# klavesnice.net
KiCad netlist of a schematic drawn in EAGLE
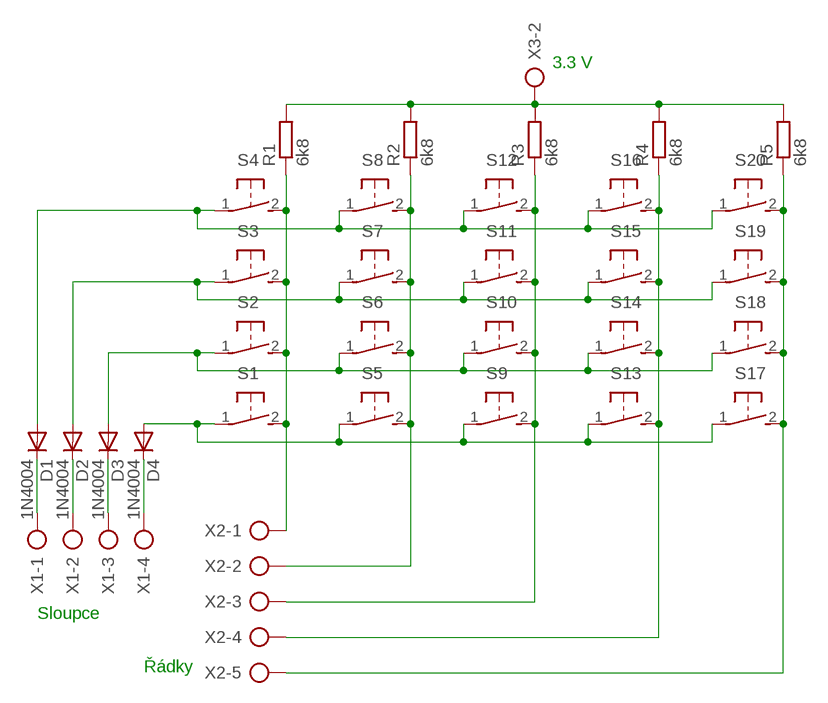
[diagram p0: schematic, sheet 1]

(export (version "E")
  (design (tool "Eeschema 10.0.6"))
  (components
    (comp (ref "D1")
      (value "1N4004")
      (footprint "eagle-import:DO41-10")
      (libsource (lib "eagle-import") (part "1N4004"))
    )
    (comp (ref "D2")
      (value "1N4004")
      (footprint "eagle-import:DO41-10")
      (libsource (lib "eagle-import") (part "1N4004"))
    )
    (comp (ref "D3")
      (value "1N4004")
      (footprint "eagle-import:DO41-10")
      (libsource (lib "eagle-import") (part "1N4004"))
    )
    (comp (ref "D4")
      (value "1N4004")
      (footprint "eagle-import:DO41-10")
      (libsource (lib "eagle-import") (part "1N4004"))
    )
    (comp (ref "R1")
      (value "6k8")
      (footprint "eagle-import:0207_12")
      (libsource (lib "eagle-import") (part "R-EU_0207/12"))
    )
    (comp (ref "R2")
      (value "6k8")
      (footprint "eagle-import:0207_12")
      (libsource (lib "eagle-import") (part "R-EU_0207/12"))
    )
    (comp (ref "R3")
      (value "6k8")
      (footprint "eagle-import:0207_12")
      (libsource (lib "eagle-import") (part "R-EU_0207/12"))
    )
    (comp (ref "R4")
      (value "6k8")
      (footprint "eagle-import:0207_12")
      (libsource (lib "eagle-import") (part "R-EU_0207/12"))
    )
    (comp (ref "R5")
      (value "6k8")
      (footprint "eagle-import:0207_12")
      (libsource (lib "eagle-import") (part "R-EU_0207/12"))
    )
    (comp (ref "S1")
      (value "31-XX")
      (footprint "eagle-import:B3F-31XX")
      (fields (field (name "MPN") "B3F-3100"))
      (libsource (lib "eagle-import") (part "31-XX"))
    )
    (comp (ref "S2")
      (value "31-XX")
      (footprint "eagle-import:B3F-31XX")
      (fields (field (name "MPN") "B3F-3100"))
      (libsource (lib "eagle-import") (part "31-XX"))
    )
    (comp (ref "S3")
      (value "31-XX")
      (footprint "eagle-import:B3F-31XX")
      (fields (field (name "MPN") "B3F-3100"))
      (libsource (lib "eagle-import") (part "31-XX"))
    )
    (comp (ref "S4")
      (value "31-XX")
      (footprint "eagle-import:B3F-31XX")
      (fields (field (name "MPN") "B3F-3100"))
      (libsource (lib "eagle-import") (part "31-XX"))
    )
    (comp (ref "S5")
      (value "31-XX")
      (footprint "eagle-import:B3F-31XX")
      (fields (field (name "MPN") "B3F-3100"))
      (libsource (lib "eagle-import") (part "31-XX"))
    )
    (comp (ref "S6")
      (value "31-XX")
      (footprint "eagle-import:B3F-31XX")
      (fields (field (name "MPN") "B3F-3100"))
      (libsource (lib "eagle-import") (part "31-XX"))
    )
    (comp (ref "S7")
      (value "31-XX")
      (footprint "eagle-import:B3F-31XX")
      (fields (field (name "MPN") "B3F-3100"))
      (libsource (lib "eagle-import") (part "31-XX"))
    )
    (comp (ref "S8")
      (value "31-XX")
      (footprint "eagle-import:B3F-31XX")
      (fields (field (name "MPN") "B3F-3100"))
      (libsource (lib "eagle-import") (part "31-XX"))
    )
    (comp (ref "S9")
      (value "31-XX")
      (footprint "eagle-import:B3F-31XX")
      (fields (field (name "MPN") "B3F-3100"))
      (libsource (lib "eagle-import") (part "31-XX"))
    )
    (comp (ref "S10")
      (value "31-XX")
      (footprint "eagle-import:B3F-31XX")
      (fields (field (name "MPN") "B3F-3100"))
      (libsource (lib "eagle-import") (part "31-XX"))
    )
    (comp (ref "S11")
      (value "31-XX")
      (footprint "eagle-import:B3F-31XX")
      (fields (field (name "MPN") "B3F-3100"))
      (libsource (lib "eagle-import") (part "31-XX"))
    )
    (comp (ref "S12")
      (value "31-XX")
      (footprint "eagle-import:B3F-31XX")
      (fields (field (name "MPN") "B3F-3100"))
      (libsource (lib "eagle-import") (part "31-XX"))
    )
    (comp (ref "S13")
      (value "31-XX")
      (footprint "eagle-import:B3F-31XX")
      (fields (field (name "MPN") "B3F-3100"))
      (libsource (lib "eagle-import") (part "31-XX"))
    )
    (comp (ref "S14")
      (value "31-XX")
      (footprint "eagle-import:B3F-31XX")
      (fields (field (name "MPN") "B3F-3100"))
      (libsource (lib "eagle-import") (part "31-XX"))
    )
    (comp (ref "S15")
      (value "31-XX")
      (footprint "eagle-import:B3F-31XX")
      (fields (field (name "MPN") "B3F-3100"))
      (libsource (lib "eagle-import") (part "31-XX"))
    )
    (comp (ref "S16")
      (value "31-XX")
      (footprint "eagle-import:B3F-31XX")
      (fields (field (name "MPN") "B3F-3100"))
      (libsource (lib "eagle-import") (part "31-XX"))
    )
    (comp (ref "S17")
      (value "31-XX")
      (footprint "eagle-import:B3F-31XX")
      (fields (field (name "MPN") "B3F-3100"))
      (libsource (lib "eagle-import") (part "31-XX"))
    )
    (comp (ref "S18")
      (value "31-XX")
      (footprint "eagle-import:B3F-31XX")
      (fields (field (name "MPN") "B3F-3100"))
      (libsource (lib "eagle-import") (part "31-XX"))
    )
    (comp (ref "S19")
      (value "31-XX")
      (footprint "eagle-import:B3F-31XX")
      (fields (field (name "MPN") "B3F-3100"))
      (libsource (lib "eagle-import") (part "31-XX"))
    )
    (comp (ref "S20")
      (value "31-XX")
      (footprint "eagle-import:B3F-31XX")
      (fields (field (name "MPN") "B3F-3100"))
      (libsource (lib "eagle-import") (part "31-XX"))
    )
    (comp (ref "X1")
      (value "AK500/4-H")
      (footprint "eagle-import:AK500_4-H")
      (libsource (lib "eagle-import") (part "AK500/4-H"))
    )
    (comp (ref "X2")
      (value "AK500/5-H")
      (footprint "eagle-import:AK500_5-H")
      (libsource (lib "eagle-import") (part "AK500/5-H"))
    )
    (comp (ref "X3")
      (value "AK500/2-H")
      (footprint "eagle-import:AK500_2-H")
      (libsource (lib "eagle-import") (part "AK500/2-H"))
    )
  )
  (nets
    (net (code "1") (name "Net-(S1-P)") (class "Default")
      (node (ref "D4") (pin "A") (pinfunction "A_A") (pintype "passive"))
      (node (ref "S1") (pin "1") (pinfunction "P_1") (pintype "passive"))
      (node (ref "S13") (pin "1") (pinfunction "P_1") (pintype "passive"))
      (node (ref "S17") (pin "1") (pinfunction "P_1") (pintype "passive"))
      (node (ref "S5") (pin "1") (pinfunction "P_1") (pintype "passive"))
      (node (ref "S9") (pin "1") (pinfunction "P_1") (pintype "passive"))
    )
    (net (code "2") (name "Net-(S1-S)") (class "Default")
      (node (ref "R1") (pin "1") (pinfunction "1_1") (pintype "passive"))
      (node (ref "S1") (pin "2") (pinfunction "S_2") (pintype "passive"))
      (node (ref "S2") (pin "2") (pinfunction "S_2") (pintype "passive"))
      (node (ref "S3") (pin "2") (pinfunction "S_2") (pintype "passive"))
      (node (ref "S4") (pin "2") (pinfunction "S_2") (pintype "passive"))
      (node (ref "X2") (pin "1") (pinfunction "KL_1") (pintype "passive"))
    )
    (net (code "3") (name "Net-(S5-S)") (class "Default")
      (node (ref "R2") (pin "1") (pinfunction "1_1") (pintype "passive"))
      (node (ref "S5") (pin "2") (pinfunction "S_2") (pintype "passive"))
      (node (ref "S6") (pin "2") (pinfunction "S_2") (pintype "passive"))
      (node (ref "S7") (pin "2") (pinfunction "S_2") (pintype "passive"))
      (node (ref "S8") (pin "2") (pinfunction "S_2") (pintype "passive"))
      (node (ref "X2") (pin "2") (pinfunction "KL_2") (pintype "passive"))
    )
    (net (code "4") (name "Net-(S10-P)") (class "Default")
      (node (ref "D3") (pin "A") (pinfunction "A_A") (pintype "passive"))
      (node (ref "S10") (pin "1") (pinfunction "P_1") (pintype "passive"))
      (node (ref "S14") (pin "1") (pinfunction "P_1") (pintype "passive"))
      (node (ref "S18") (pin "1") (pinfunction "P_1") (pintype "passive"))
      (node (ref "S2") (pin "1") (pinfunction "P_1") (pintype "passive"))
      (node (ref "S6") (pin "1") (pinfunction "P_1") (pintype "passive"))
    )
    (net (code "5") (name "Net-(S10-S)") (class "Default")
      (node (ref "R3") (pin "1") (pinfunction "1_1") (pintype "passive"))
      (node (ref "S10") (pin "2") (pinfunction "S_2") (pintype "passive"))
      (node (ref "S11") (pin "2") (pinfunction "S_2") (pintype "passive"))
      (node (ref "S12") (pin "2") (pinfunction "S_2") (pintype "passive"))
      (node (ref "S9") (pin "2") (pinfunction "S_2") (pintype "passive"))
      (node (ref "X2") (pin "3") (pinfunction "KL_3") (pintype "passive"))
    )
    (net (code "6") (name "Net-(S11-P)") (class "Default")
      (node (ref "D2") (pin "A") (pinfunction "A_A") (pintype "passive"))
      (node (ref "S11") (pin "1") (pinfunction "P_1") (pintype "passive"))
      (node (ref "S15") (pin "1") (pinfunction "P_1") (pintype "passive"))
      (node (ref "S19") (pin "1") (pinfunction "P_1") (pintype "passive"))
      (node (ref "S3") (pin "1") (pinfunction "P_1") (pintype "passive"))
      (node (ref "S7") (pin "1") (pinfunction "P_1") (pintype "passive"))
    )
    (net (code "7") (name "Net-(S12-P)") (class "Default")
      (node (ref "D1") (pin "A") (pinfunction "A_A") (pintype "passive"))
      (node (ref "S12") (pin "1") (pinfunction "P_1") (pintype "passive"))
      (node (ref "S16") (pin "1") (pinfunction "P_1") (pintype "passive"))
      (node (ref "S20") (pin "1") (pinfunction "P_1") (pintype "passive"))
      (node (ref "S4") (pin "1") (pinfunction "P_1") (pintype "passive"))
      (node (ref "S8") (pin "1") (pinfunction "P_1") (pintype "passive"))
    )
    (net (code "8") (name "Net-(S13-S)") (class "Default")
      (node (ref "R4") (pin "1") (pinfunction "1_1") (pintype "passive"))
      (node (ref "S13") (pin "2") (pinfunction "S_2") (pintype "passive"))
      (node (ref "S14") (pin "2") (pinfunction "S_2") (pintype "passive"))
      (node (ref "S15") (pin "2") (pinfunction "S_2") (pintype "passive"))
      (node (ref "S16") (pin "2") (pinfunction "S_2") (pintype "passive"))
      (node (ref "X2") (pin "4") (pinfunction "KL_4") (pintype "passive"))
    )
    (net (code "9") (name "Net-(S17-S)") (class "Default")
      (node (ref "R5") (pin "1") (pinfunction "1_1") (pintype "passive"))
      (node (ref "S17") (pin "2") (pinfunction "S_2") (pintype "passive"))
      (node (ref "S18") (pin "2") (pinfunction "S_2") (pintype "passive"))
      (node (ref "S19") (pin "2") (pinfunction "S_2") (pintype "passive"))
      (node (ref "S20") (pin "2") (pinfunction "S_2") (pintype "passive"))
      (node (ref "X2") (pin "5") (pinfunction "KL_5") (pintype "passive"))
    )
    (net (code "10") (name "Net-(X1A-KL)") (class "Default")
      (node (ref "D1") (pin "C") (pinfunction "C_C") (pintype "passive"))
      (node (ref "X1") (pin "1") (pinfunction "KL_1") (pintype "passive"))
    )
    (net (code "11") (name "Net-(X1B-KL)") (class "Default")
      (node (ref "D2") (pin "C") (pinfunction "C_C") (pintype "passive"))
      (node (ref "X1") (pin "2") (pinfunction "KL_2") (pintype "passive"))
    )
    (net (code "12") (name "Net-(X1C-KL)") (class "Default")
      (node (ref "D3") (pin "C") (pinfunction "C_C") (pintype "passive"))
      (node (ref "X1") (pin "3") (pinfunction "KL_3") (pintype "passive"))
    )
    (net (code "13") (name "Net-(X1D-KL)") (class "Default")
      (node (ref "D4") (pin "C") (pinfunction "C_C") (pintype "passive"))
      (node (ref "X1") (pin "4") (pinfunction "KL_4") (pintype "passive"))
    )
    (net (code "14") (name "Net-(X3B-KL)") (class "Default")
      (node (ref "R1") (pin "2") (pinfunction "2_2") (pintype "passive"))
      (node (ref "R2") (pin "2") (pinfunction "2_2") (pintype "passive"))
      (node (ref "R3") (pin "2") (pinfunction "2_2") (pintype "passive"))
      (node (ref "R4") (pin "2") (pinfunction "2_2") (pintype "passive"))
      (node (ref "R5") (pin "2") (pinfunction "2_2") (pintype "passive"))
      (node (ref "X3") (pin "2") (pinfunction "KL_2") (pintype "passive"))
    )
  )
)
